# 6_-OPI_POWER.net
KiCad netlist of a schematic drawn in Altium Designer
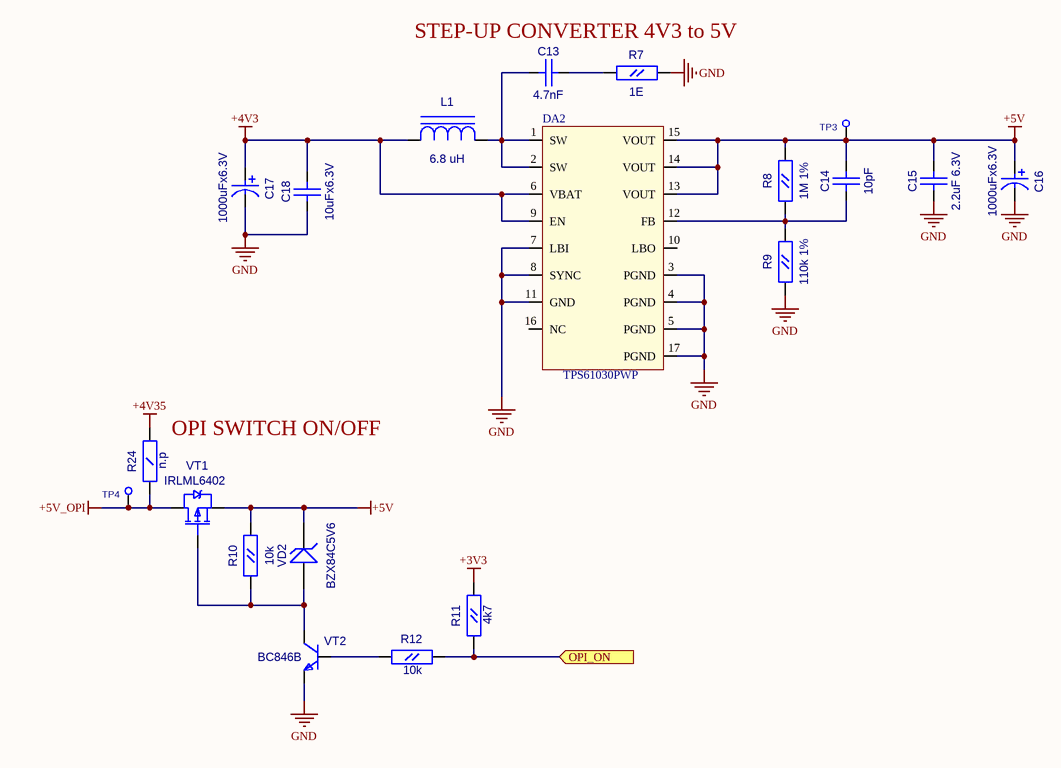
[diagram p0: [6]-OPI_POWER.SchDoc]

(export (version "E")
  (design (tool "Eeschema 10.0.6"))
  (components
    (comp (ref "C13")
      (value "4.7nF")
      (footprint "CC0603")
      (description "CC0603")
      (libsource (lib "gprs_modem_2") (part "CC0603"))
    )
    (comp (ref "C14")
      (value "10pF")
      (footprint "CC0603")
      (description "CC0603")
      (libsource (lib "gprs_modem_2") (part "CC0603"))
    )
    (comp (ref "C15")
      (value "2.2uF 6.3V")
      (footprint "CC0805")
      (description "CC0805")
      (libsource (lib "gprs_modem_2") (part "CC0805"))
    )
    (comp (ref "C16")
      (value "1000uFx6.3V")
      (footprint "CC8X3.5")
      (description "CAP0.35")
      (libsource (lib "gprs_modem_2") (part "CAP0.35"))
    )
    (comp (ref "C17")
      (value "1000uFx6.3V")
      (footprint "CC8X3.5")
      (description "CAP0.35")
      (libsource (lib "gprs_modem_2") (part "CAP0.35"))
    )
    (comp (ref "C18")
      (value "10uFx6.3V")
      (footprint "CC0805")
      (description "CC0805")
      (libsource (lib "gprs_modem_2") (part "CC0805"))
    )
    (comp (ref "DA2")
      (value "TPS61030PWP")
      (footprint "R-PDSO-G16")
      (description "Boost converter")
      (libsource (lib "gprs_modem") (part "TPS61030PWP"))
    )
    (comp (ref "L1")
      (value "6.8 uH")
      (footprint "SDR0805")
      (description "SDR0805")
      (libsource (lib "gprs_modem_2") (part "SDR0805"))
    )
    (comp (ref "R7")
      (value "1E")
      (footprint "RC0603")
      (description "RC0603")
      (libsource (lib "gprs_modem_2") (part "RC0603"))
    )
    (comp (ref "R8")
      (value "1M 1%")
      (footprint "RC0603")
      (description "RC0603")
      (libsource (lib "gprs_modem_2") (part "RC0603"))
    )
    (comp (ref "R9")
      (value "110k 1%")
      (footprint "RC0603")
      (description "RC0603")
      (libsource (lib "gprs_modem_2") (part "RC0603"))
    )
    (comp (ref "R10")
      (value "10k")
      (footprint "RC0603")
      (description "RC0603")
      (libsource (lib "gprs_modem_2") (part "RC0603"))
    )
    (comp (ref "R11")
      (value "4k7")
      (footprint "RC0603")
      (description "RC0603")
      (libsource (lib "fizik_lib") (part "RC0603"))
    )
    (comp (ref "R12")
      (value "10k")
      (footprint "RC0603")
      (description "RC0603")
      (libsource (lib "fizik_lib") (part "RC0603"))
    )
    (comp (ref "R24")
      (value "n.p")
      (footprint "RC1206")
      (description "RC1206")
      (libsource (lib "fizik_lib") (part "RC1206"))
    )
    (comp (ref "TP3")
      (value "TESTPOINT1")
      (footprint "TESTPOINT1")
      (libsource (lib "fizik_lib") (part "TESTPOINT1"))
    )
    (comp (ref "TP4")
      (value "TESTPOINT1")
      (footprint "TESTPOINT1")
      (libsource (lib "fizik_lib") (part "TESTPOINT1"))
    )
    (comp (ref "VD2")
      (value "BZX84C5V6")
      (footprint "SOT-23(123)")
      (description "Zener Voltage Regulator Diode")
      (libsource (lib "gprs_modem_2") (part "BZX84"))
    )
    (comp (ref "VT1")
      (value "IRLML6402")
      (footprint "SOT-23(123)")
      (description "HEXFET Power MOSFET")
      (libsource (lib "gprs_modem_2") (part "IRLML6402"))
    )
    (comp (ref "VT2")
      (value "BC846B")
      (footprint "SOT-23(123)")
      (description "BC846BLT1")
      (libsource (lib "gprs_modem_2") (part "BC846BLT1"))
    )
  )
  (nets
    (net (code "1") (name "+3V3") (class "Default")
      (node (ref "R11") (pin "2") (pinfunction "B_2") (pintype "passive"))
    )
    (net (code "2") (name "+4V3") (class "Default")
      (node (ref "C17") (pin "1") (pintype "passive"))
      (node (ref "C18") (pin "2") (pinfunction "B_2") (pintype "passive"))
      (node (ref "DA2") (pin "6") (pinfunction "VBAT_6") (pintype "passive"))
      (node (ref "DA2") (pin "9") (pinfunction "EN_9") (pintype "passive"))
      (node (ref "L1") (pin "1") (pinfunction "C_1") (pintype "passive"))
    )
    (net (code "3") (name "+4V35") (class "Default")
      (node (ref "R24") (pin "2") (pinfunction "B_2") (pintype "passive"))
    )
    (net (code "4") (name "+5V") (class "Default")
      (node (ref "C14") (pin "2") (pinfunction "B_2") (pintype "passive"))
      (node (ref "C15") (pin "2") (pinfunction "B_2") (pintype "passive"))
      (node (ref "C16") (pin "1") (pintype "passive"))
      (node (ref "DA2") (pin "13") (pinfunction "VOUT_13") (pintype "passive"))
      (node (ref "DA2") (pin "14") (pinfunction "VOUT_14") (pintype "passive"))
      (node (ref "DA2") (pin "15") (pinfunction "VOUT_15") (pintype "passive"))
      (node (ref "R10") (pin "2") (pinfunction "B_2") (pintype "passive"))
      (node (ref "R8") (pin "2") (pinfunction "B_2") (pintype "passive"))
      (node (ref "TP3") (pin "1") (pintype "passive"))
      (node (ref "VD2") (pin "3") (pinfunction "K_3") (pintype "passive"))
      (node (ref "VT1") (pin "2") (pinfunction "S_2") (pintype "passive"))
    )
    (net (code "5") (name "+5V_OPI") (class "Default")
      (node (ref "R24") (pin "1") (pinfunction "A_1") (pintype "passive"))
      (node (ref "TP4") (pin "1") (pintype "passive"))
      (node (ref "VT1") (pin "3") (pinfunction "D_3") (pintype "passive"))
    )
    (net (code "6") (name "/OPI_ON") (class "Default")
      (node (ref "R11") (pin "1") (pinfunction "A_1") (pintype "passive"))
      (node (ref "R12") (pin "2") (pinfunction "B_2") (pintype "passive"))
    )
    (net (code "7") (name "GND") (class "Default")
      (node (ref "C15") (pin "1") (pinfunction "A_1") (pintype "passive"))
      (node (ref "C16") (pin "2") (pintype "passive"))
      (node (ref "C17") (pin "2") (pintype "passive"))
      (node (ref "C18") (pin "1") (pinfunction "A_1") (pintype "passive"))
      (node (ref "DA2") (pin "11") (pinfunction "GND_11") (pintype "passive"))
      (node (ref "DA2") (pin "17") (pinfunction "PGND_17") (pintype "passive"))
      (node (ref "DA2") (pin "3") (pinfunction "PGND_3") (pintype "passive"))
      (node (ref "DA2") (pin "4") (pinfunction "PGND_4") (pintype "passive"))
      (node (ref "DA2") (pin "5") (pinfunction "PGND_5") (pintype "passive"))
      (node (ref "DA2") (pin "7") (pinfunction "LBI_7") (pintype "passive"))
      (node (ref "DA2") (pin "8") (pinfunction "SYNC_8") (pintype "passive"))
      (node (ref "R7") (pin "2") (pinfunction "B_2") (pintype "passive"))
      (node (ref "R9") (pin "1") (pinfunction "A_1") (pintype "passive"))
      (node (ref "VT2") (pin "2") (pinfunction "E_2") (pintype "passive"))
    )
    (net (code "8") (name "Net-(C13-A)") (class "Default")
      (node (ref "C13") (pin "1") (pinfunction "A_1") (pintype "passive"))
      (node (ref "DA2") (pin "1") (pinfunction "SW_1") (pintype "passive"))
      (node (ref "DA2") (pin "2") (pinfunction "SW_2") (pintype "passive"))
      (node (ref "L1") (pin "2") (pinfunction "A_2") (pintype "passive"))
    )
    (net (code "9") (name "Net-(C13-B)") (class "Default")
      (node (ref "C13") (pin "2") (pinfunction "B_2") (pintype "passive"))
      (node (ref "R7") (pin "1") (pinfunction "A_1") (pintype "passive"))
    )
    (net (code "10") (name "Net-(C14-A)") (class "Default")
      (node (ref "C14") (pin "1") (pinfunction "A_1") (pintype "passive"))
      (node (ref "DA2") (pin "12") (pinfunction "FB_12") (pintype "passive"))
      (node (ref "R8") (pin "1") (pinfunction "A_1") (pintype "passive"))
      (node (ref "R9") (pin "2") (pinfunction "B_2") (pintype "passive"))
    )
    (net (code "11") (name "Net-(R10-A)") (class "Default")
      (node (ref "R10") (pin "1") (pinfunction "A_1") (pintype "passive"))
      (node (ref "VD2") (pin "1") (pinfunction "A_1") (pintype "passive"))
      (node (ref "VT1") (pin "1") (pinfunction "G_1") (pintype "passive"))
      (node (ref "VT2") (pin "3") (pinfunction "C_3") (pintype "passive"))
    )
    (net (code "12") (name "Net-(R12-A)") (class "Default")
      (node (ref "R12") (pin "1") (pinfunction "A_1") (pintype "passive"))
      (node (ref "VT2") (pin "1") (pinfunction "B_1") (pintype "passive"))
    )
    (net (code "13") (name "unconnected-(DA2-LBO-Pad10)") (class "Default")
      (node (ref "DA2") (pin "10") (pinfunction "LBO_10") (pintype "passive"))
    )
    (net (code "14") (name "unconnected-(DA2-NC-Pad16)") (class "Default")
      (node (ref "DA2") (pin "16") (pinfunction "NC_16") (pintype "passive"))
    )
  )
)
